# Naninator.net
KiCad netlist of a schematic drawn in EAGLE
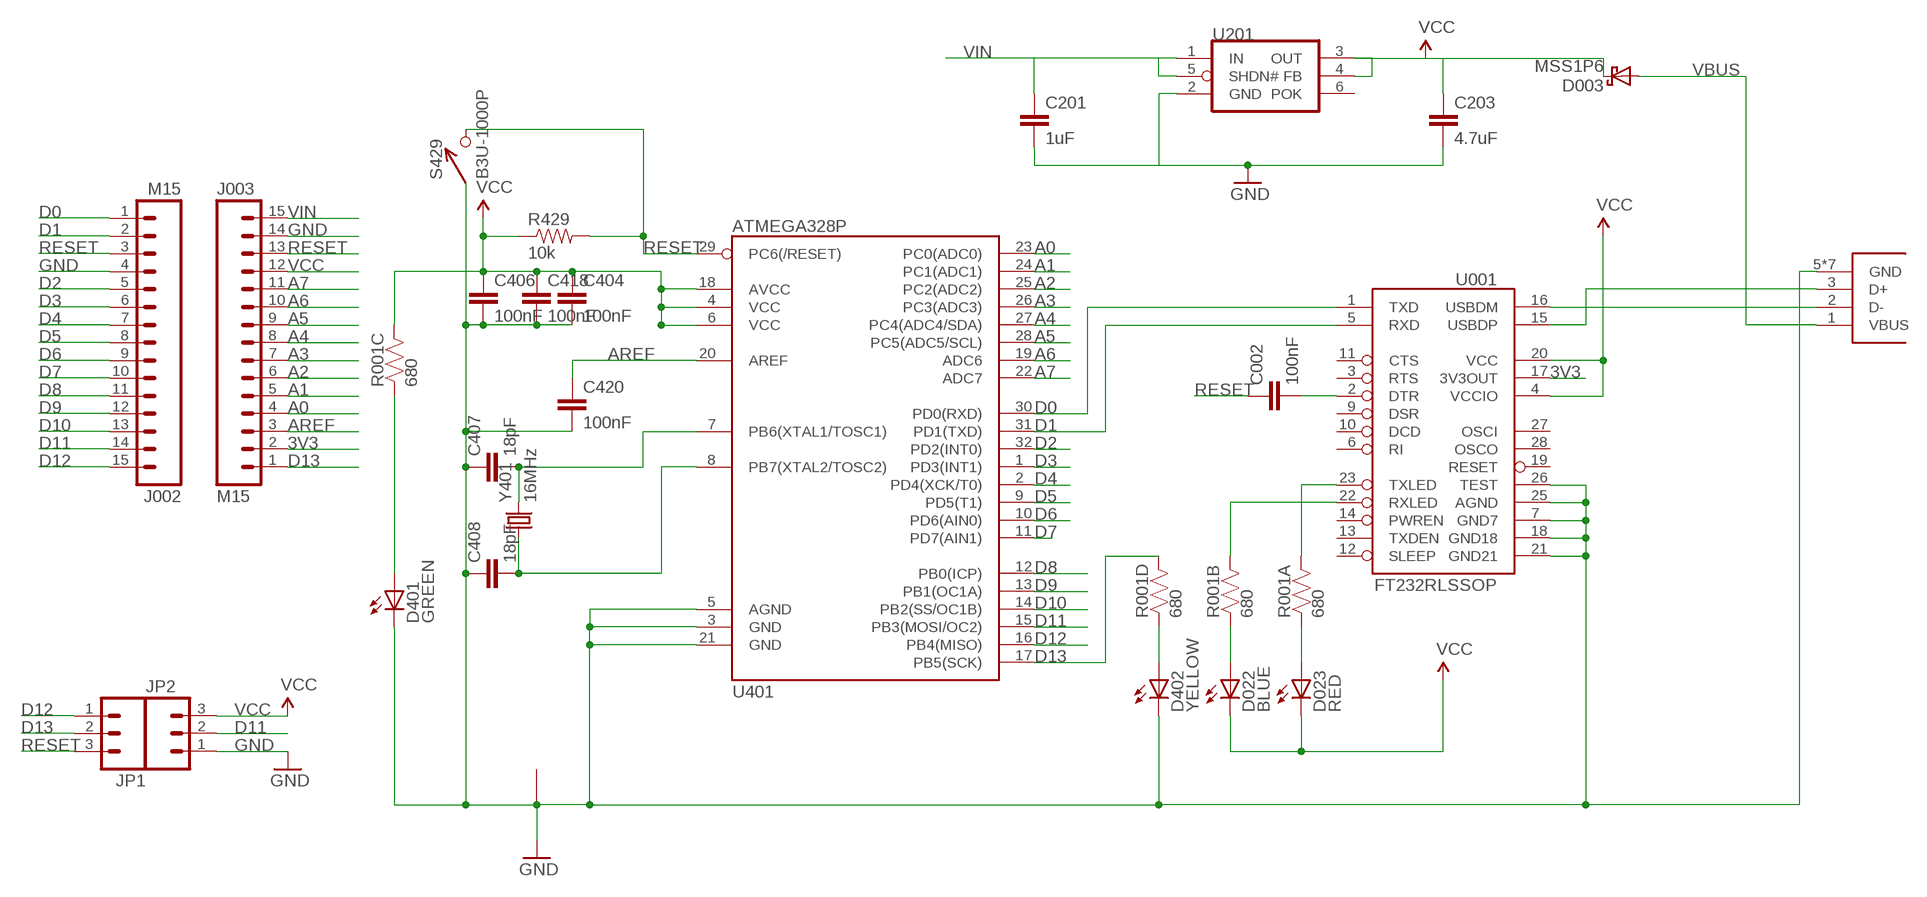
[diagram p0: schematic, sheet 1]

(export (version "E")
  (design (tool "Eeschema 10.0.6"))
  (components
    (comp (ref "C002")
      (value "100nF")
      (footprint "eagle-import:0402-CAP")
      (libsource (lib "eagle-import") (part "CAP0402-CAP"))
    )
    (comp (ref "C201")
      (value "1uF")
      (footprint "eagle-import:0402-CAP")
      (libsource (lib "eagle-import") (part "CAP0402-CAP"))
    )
    (comp (ref "C203")
      (value "4.7uF")
      (footprint "eagle-import:0402-CAP")
      (libsource (lib "eagle-import") (part "CAP0402-CAP"))
    )
    (comp (ref "C404")
      (value "100nF")
      (footprint "eagle-import:0402-CAP")
      (libsource (lib "eagle-import") (part "CAP0402-CAP"))
    )
    (comp (ref "C406")
      (value "100nF")
      (footprint "eagle-import:0402-CAP")
      (libsource (lib "eagle-import") (part "CAP0402-CAP"))
    )
    (comp (ref "C407")
      (value "18pF")
      (footprint "eagle-import:0402-CAP")
      (libsource (lib "eagle-import") (part "CAP0402-CAP"))
    )
    (comp (ref "C408")
      (value "18pF")
      (footprint "eagle-import:0402-CAP")
      (libsource (lib "eagle-import") (part "CAP0402-CAP"))
    )
    (comp (ref "C418")
      (value "100nF")
      (footprint "eagle-import:0402-CAP")
      (libsource (lib "eagle-import") (part "CAP0402-CAP"))
    )
    (comp (ref "C420")
      (value "100nF")
      (footprint "eagle-import:0402-CAP")
      (libsource (lib "eagle-import") (part "CAP0402-CAP"))
    )
    (comp (ref "D003")
      (value "MSS1P6")
      (footprint "eagle-import:MICROSMP")
      (libsource (lib "eagle-import") (part "MSS1P6"))
    )
    (comp (ref "D022")
      (value "BLUE")
      (footprint "eagle-import:LED-0603")
      (libsource (lib "eagle-import") (part "LED0603"))
    )
    (comp (ref "D023")
      (value "RED")
      (footprint "eagle-import:LED-0603")
      (libsource (lib "eagle-import") (part "LED0603"))
    )
    (comp (ref "D401")
      (value "GREEN")
      (footprint "eagle-import:LED-0603")
      (libsource (lib "eagle-import") (part "LED0603"))
    )
    (comp (ref "D402")
      (value "YELLOW")
      (footprint "eagle-import:LED-0603")
      (libsource (lib "eagle-import") (part "LED0603"))
    )
    (comp (ref "J001")
      (value "USB_MICROB_JST")
      (footprint "eagle-import:UB-MC5BR3-SD204-4S")
      (libsource (lib "eagle-import") (part "USB_MICROB_JST"))
    )
    (comp (ref "J002")
      (value "M15")
      (footprint "eagle-import:1X15")
      (libsource (lib "eagle-import") (part "M15"))
    )
    (comp (ref "J003")
      (value "M15")
      (footprint "eagle-import:1X15")
      (libsource (lib "eagle-import") (part "M15"))
    )
    (comp (ref "JP1")
      (value "M03PTH")
      (footprint "eagle-import:1X03")
      (libsource (lib "eagle-import") (part "M03PTH"))
    )
    (comp (ref "JP2")
      (value "M03PTH")
      (footprint "eagle-import:1X03")
      (libsource (lib "eagle-import") (part "M03PTH"))
    )
    (comp (ref "R001")
      (value "680")
      (footprint "eagle-import:CRA04")
      (fields (field (name "DIGIKEY") "CRA4S8680CT-ND"))
      (libsource (lib "eagle-import") (part "RP404"))
    )
    (comp (ref "R429")
      (value "10k")
      (footprint "eagle-import:0402-RES")
      (libsource (lib "eagle-import") (part "RESISTOR0402-RES"))
    )
    (comp (ref "S429")
      (value "B3U-1000P")
      (footprint "eagle-import:B3U-1000P")
      (libsource (lib "eagle-import") (part "B3U-1000P"))
    )
    (comp (ref "U001")
      (value "FT232RLSSOP")
      (footprint "eagle-import:SSOP28DB")
      (libsource (lib "eagle-import") (part "FT232RLSSOP"))
    )
    (comp (ref "U201")
      (value "MAX8881")
      (footprint "eagle-import:SOT-23-6")
      (libsource (lib "eagle-import") (part "MAX8881"))
    )
    (comp (ref "U401")
      (value "ATMEGA328P")
      (footprint "eagle-import:TQFP32-08")
      (libsource (lib "eagle-import") (part "ATMEGA168"))
    )
    (comp (ref "Y401")
      (value "16MHz")
      (footprint "eagle-import:CRYSTAL_SMD_2MM_2_5MM")
      (fields (field (name "DIGIKEY") "478-6955-1-ND"))
      (libsource (lib "eagle-import") (part "CX2520"))
    )
  )
  (nets
    (net (code "1") (name "/3V3") (class "Default")
      (node (ref "J003") (pin "2") (pinfunction "2_2") (pintype "passive"))
      (node (ref "U001") (pin "17") (pinfunction "3V3OUT_17") (pintype "output"))
    )
    (net (code "2") (name "/A0") (class "Default")
      (node (ref "J003") (pin "4") (pinfunction "4_4") (pintype "passive"))
      (node (ref "U401") (pin "23") (pinfunction "PC0(ADC0)_23") (pintype "bidirectional"))
    )
    (net (code "3") (name "/A1") (class "Default")
      (node (ref "J003") (pin "5") (pinfunction "5_5") (pintype "passive"))
      (node (ref "U401") (pin "24") (pinfunction "PC1(ADC1)_24") (pintype "bidirectional"))
    )
    (net (code "4") (name "/A2") (class "Default")
      (node (ref "J003") (pin "6") (pinfunction "6_6") (pintype "passive"))
      (node (ref "U401") (pin "25") (pinfunction "PC2(ADC2)_25") (pintype "bidirectional"))
    )
    (net (code "5") (name "/A3") (class "Default")
      (node (ref "J003") (pin "7") (pinfunction "7_7") (pintype "passive"))
      (node (ref "U401") (pin "26") (pinfunction "PC3(ADC3)_26") (pintype "bidirectional"))
    )
    (net (code "6") (name "/A4") (class "Default")
      (node (ref "J003") (pin "8") (pinfunction "8_8") (pintype "passive"))
      (node (ref "U401") (pin "27") (pinfunction "PC4(ADC4/SDA)_27") (pintype "bidirectional"))
    )
    (net (code "7") (name "/A5") (class "Default")
      (node (ref "J003") (pin "9") (pinfunction "9_9") (pintype "passive"))
      (node (ref "U401") (pin "28") (pinfunction "PC5(ADC5/SCL)_28") (pintype "bidirectional"))
    )
    (net (code "8") (name "/A6") (class "Default")
      (node (ref "J003") (pin "10") (pinfunction "10_10") (pintype "passive"))
      (node (ref "U401") (pin "19") (pinfunction "ADC6_19") (pintype "bidirectional"))
    )
    (net (code "9") (name "/A7") (class "Default")
      (node (ref "J003") (pin "11") (pinfunction "11_11") (pintype "passive"))
      (node (ref "U401") (pin "22") (pinfunction "ADC7_22") (pintype "bidirectional"))
    )
    (net (code "10") (name "/AREF") (class "Default")
      (node (ref "C420") (pin "1") (pinfunction "1_1") (pintype "passive"))
      (node (ref "J003") (pin "3") (pinfunction "3_3") (pintype "passive"))
      (node (ref "U401") (pin "20") (pinfunction "AREF_20") (pintype "bidirectional"))
    )
    (net (code "11") (name "/D0") (class "Default")
      (node (ref "J002") (pin "1") (pinfunction "1_1") (pintype "passive"))
      (node (ref "U001") (pin "1") (pinfunction "TXD_1") (pintype "output"))
      (node (ref "U401") (pin "30") (pinfunction "PD0(RXD)_30") (pintype "bidirectional"))
    )
    (net (code "12") (name "/D1") (class "Default")
      (node (ref "J002") (pin "2") (pinfunction "2_2") (pintype "passive"))
      (node (ref "U001") (pin "5") (pinfunction "RXD_5") (pintype "input"))
      (node (ref "U401") (pin "31") (pinfunction "PD1(TXD)_31") (pintype "bidirectional"))
    )
    (net (code "13") (name "/D2") (class "Default")
      (node (ref "J002") (pin "5") (pinfunction "5_5") (pintype "passive"))
      (node (ref "U401") (pin "32") (pinfunction "PD2(INT0)_32") (pintype "bidirectional"))
    )
    (net (code "14") (name "/D3") (class "Default")
      (node (ref "J002") (pin "6") (pinfunction "6_6") (pintype "passive"))
      (node (ref "U401") (pin "1") (pinfunction "PD3(INT1)_1") (pintype "bidirectional"))
    )
    (net (code "15") (name "/D4") (class "Default")
      (node (ref "J002") (pin "7") (pinfunction "7_7") (pintype "passive"))
      (node (ref "U401") (pin "2") (pinfunction "PD4(XCK/T0)_2") (pintype "bidirectional"))
    )
    (net (code "16") (name "/D5") (class "Default")
      (node (ref "J002") (pin "8") (pinfunction "8_8") (pintype "passive"))
      (node (ref "U401") (pin "9") (pinfunction "PD5(T1)_9") (pintype "bidirectional"))
    )
    (net (code "17") (name "/D6") (class "Default")
      (node (ref "J002") (pin "9") (pinfunction "9_9") (pintype "passive"))
      (node (ref "U401") (pin "10") (pinfunction "PD6(AIN0)_10") (pintype "bidirectional"))
    )
    (net (code "18") (name "/D7") (class "Default")
      (node (ref "J002") (pin "10") (pinfunction "10_10") (pintype "passive"))
      (node (ref "U401") (pin "11") (pinfunction "PD7(AIN1)_11") (pintype "bidirectional"))
    )
    (net (code "19") (name "/D8") (class "Default")
      (node (ref "J002") (pin "11") (pinfunction "11_11") (pintype "passive"))
      (node (ref "U401") (pin "12") (pinfunction "PB0(ICP)_12") (pintype "bidirectional"))
    )
    (net (code "20") (name "/D9") (class "Default")
      (node (ref "J002") (pin "12") (pinfunction "12_12") (pintype "passive"))
      (node (ref "U401") (pin "13") (pinfunction "PB1(OC1A)_13") (pintype "bidirectional"))
    )
    (net (code "21") (name "/D10") (class "Default")
      (node (ref "J002") (pin "13") (pinfunction "13_13") (pintype "passive"))
      (node (ref "U401") (pin "14") (pinfunction "PB2(SS/OC1B)_14") (pintype "bidirectional"))
    )
    (net (code "22") (name "/D11") (class "Default")
      (node (ref "J002") (pin "14") (pinfunction "14_14") (pintype "passive"))
      (node (ref "JP2") (pin "2") (pinfunction "2_2") (pintype "passive"))
      (node (ref "U401") (pin "15") (pinfunction "PB3(MOSI/OC2)_15") (pintype "bidirectional"))
    )
    (net (code "23") (name "/D12") (class "Default")
      (node (ref "J002") (pin "15") (pinfunction "15_15") (pintype "passive"))
      (node (ref "JP1") (pin "1") (pinfunction "1_1") (pintype "passive"))
      (node (ref "U401") (pin "16") (pinfunction "PB4(MISO)_16") (pintype "bidirectional"))
    )
    (net (code "24") (name "/D13") (class "Default")
      (node (ref "J003") (pin "1") (pinfunction "1_1") (pintype "passive"))
      (node (ref "JP1") (pin "2") (pinfunction "2_2") (pintype "passive"))
      (node (ref "R001") (pin "5") (pinfunction "2_5") (pintype "passive"))
      (node (ref "U401") (pin "17") (pinfunction "PB5(SCK)_17") (pintype "bidirectional"))
    )
    (net (code "25") (name "/RESET") (class "Default")
      (node (ref "C002") (pin "1") (pinfunction "1_1") (pintype "passive"))
      (node (ref "J002") (pin "3") (pinfunction "3_3") (pintype "passive"))
      (node (ref "J003") (pin "13") (pinfunction "13_13") (pintype "passive"))
      (node (ref "JP1") (pin "3") (pinfunction "3_3") (pintype "passive"))
      (node (ref "R429") (pin "2") (pinfunction "2_2") (pintype "passive"))
      (node (ref "S429") (pin "P$2") (pinfunction "2_P$2") (pintype "bidirectional"))
      (node (ref "U401") (pin "29") (pinfunction "PC6(/RESET)_29") (pintype "bidirectional"))
    )
    (net (code "26") (name "/VBUS") (class "Default")
      (node (ref "D003") (pin "A") (pinfunction "A_A") (pintype "passive"))
      (node (ref "J001") (pin "1") (pinfunction "VBUS_1") (pintype "bidirectional"))
    )
    (net (code "27") (name "/VIN") (class "Default")
      (node (ref "C201") (pin "1") (pinfunction "1_1") (pintype "passive"))
      (node (ref "J003") (pin "15") (pinfunction "15_15") (pintype "passive"))
      (node (ref "U201") (pin "1") (pinfunction "IN_1") (pintype "bidirectional"))
      (node (ref "U201") (pin "5") (pinfunction "SHDN#_5") (pintype "bidirectional"))
    )
    (net (code "28") (name "GND") (class "Default")
      (node (ref "C201") (pin "2") (pinfunction "2_2") (pintype "passive"))
      (node (ref "C203") (pin "2") (pinfunction "2_2") (pintype "passive"))
      (node (ref "C404") (pin "2") (pinfunction "2_2") (pintype "passive"))
      (node (ref "C406") (pin "2") (pinfunction "2_2") (pintype "passive"))
      (node (ref "C407") (pin "1") (pinfunction "1_1") (pintype "passive"))
      (node (ref "C408") (pin "1") (pinfunction "1_1") (pintype "passive"))
      (node (ref "C418") (pin "2") (pinfunction "2_2") (pintype "passive"))
      (node (ref "C420") (pin "2") (pinfunction "2_2") (pintype "passive"))
      (node (ref "D401") (pin "C") (pinfunction "C_C") (pintype "passive"))
      (node (ref "D402") (pin "C") (pinfunction "C_C") (pintype "passive"))
      (node (ref "J001") (pin "5") (pinfunction "GND_5") (pintype "bidirectional"))
      (node (ref "J001") (pin "P$10") (pinfunction "GND_P$10") (pintype "bidirectional"))
      (node (ref "J001") (pin "P$11") (pinfunction "GND_P$11") (pintype "bidirectional"))
      (node (ref "J001") (pin "P$6") (pinfunction "GND_P$6") (pintype "bidirectional"))
      (node (ref "J001") (pin "P$7") (pinfunction "GND_P$7") (pintype "bidirectional"))
      (node (ref "J001") (pin "P$8") (pinfunction "GND_P$8") (pintype "bidirectional"))
      (node (ref "J001") (pin "P$9") (pinfunction "GND_P$9") (pintype "bidirectional"))
      (node (ref "J002") (pin "4") (pinfunction "4_4") (pintype "passive"))
      (node (ref "J003") (pin "14") (pinfunction "14_14") (pintype "passive"))
      (node (ref "JP2") (pin "1") (pinfunction "1_1") (pintype "passive"))
      (node (ref "S429") (pin "P$1") (pinfunction "1_P$1") (pintype "bidirectional"))
      (node (ref "U001") (pin "18") (pinfunction "GND18_18") (pintype "power_in"))
      (node (ref "U001") (pin "21") (pinfunction "GND21_21") (pintype "power_in"))
      (node (ref "U001") (pin "25") (pinfunction "AGND_25") (pintype "power_in"))
      (node (ref "U001") (pin "26") (pinfunction "TEST_26") (pintype "input"))
      (node (ref "U001") (pin "7") (pinfunction "GND7_7") (pintype "power_in"))
      (node (ref "U201") (pin "2") (pinfunction "GND_2") (pintype "bidirectional"))
      (node (ref "U401") (pin "21") (pinfunction "GND_21") (pintype "bidirectional"))
      (node (ref "U401") (pin "3") (pinfunction "GND_3") (pintype "bidirectional"))
      (node (ref "U401") (pin "5") (pinfunction "AGND_5") (pintype "bidirectional"))
      (node (ref "Y401") (pin "2") (pinfunction "1_2") (pintype "bidirectional"))
      (node (ref "Y401") (pin "4") (pinfunction "1_4") (pintype "bidirectional"))
    )
    (net (code "29") (name "Net-(D023-PadA)") (class "Default")
      (node (ref "D023") (pin "A") (pinfunction "A_A") (pintype "passive"))
      (node (ref "R001") (pin "1") (pinfunction "1_1") (pintype "passive"))
    )
    (net (code "30") (name "Net-(J001-D+)") (class "Default")
      (node (ref "J001") (pin "3") (pinfunction "D+_3") (pintype "bidirectional"))
      (node (ref "U001") (pin "15") (pinfunction "USBDP_15") (pintype "bidirectional"))
    )
    (net (code "31") (name "Net-(J001-D-)") (class "Default")
      (node (ref "J001") (pin "2") (pinfunction "D-_2") (pintype "bidirectional"))
      (node (ref "U001") (pin "16") (pinfunction "USBDM_16") (pintype "bidirectional"))
    )
    (net (code "32") (name "Net-(R001A-2)") (class "Default")
      (node (ref "R001") (pin "8") (pinfunction "2_8") (pintype "passive"))
      (node (ref "U001") (pin "23") (pinfunction "TXLED_23") (pintype "input"))
    )
    (net (code "33") (name "Net-(R001B-1)") (class "Default")
      (node (ref "D022") (pin "A") (pinfunction "A_A") (pintype "passive"))
      (node (ref "R001") (pin "2") (pinfunction "1_2") (pintype "passive"))
    )
    (net (code "34") (name "Net-(R001B-2)") (class "Default")
      (node (ref "R001") (pin "7") (pinfunction "2_7") (pintype "passive"))
      (node (ref "U001") (pin "22") (pinfunction "RXLED_22") (pintype "input"))
    )
    (net (code "35") (name "Net-(R001C-1)") (class "Default")
      (node (ref "D401") (pin "A") (pinfunction "A_A") (pintype "passive"))
      (node (ref "R001") (pin "3") (pinfunction "1_3") (pintype "passive"))
    )
    (net (code "36") (name "Net-(R001D-1)") (class "Default")
      (node (ref "D402") (pin "A") (pinfunction "A_A") (pintype "passive"))
      (node (ref "R001") (pin "4") (pinfunction "1_4") (pintype "passive"))
    )
    (net (code "37") (name "Net-(U001-DTR)") (class "Default")
      (node (ref "C002") (pin "2") (pinfunction "2_2") (pintype "passive"))
      (node (ref "U001") (pin "2") (pinfunction "DTR_2") (pintype "output"))
    )
    (net (code "38") (name "Net-(U401-PB6(XTAL1{slash}TOSC1))") (class "Default")
      (node (ref "C407") (pin "2") (pinfunction "2_2") (pintype "passive"))
      (node (ref "U401") (pin "7") (pinfunction "PB6(XTAL1/TOSC1)_7") (pintype "bidirectional"))
      (node (ref "Y401") (pin "3") (pinfunction "2_3") (pintype "passive"))
    )
    (net (code "39") (name "Net-(U401-PB7(XTAL2{slash}TOSC2))") (class "Default")
      (node (ref "C408") (pin "2") (pinfunction "2_2") (pintype "passive"))
      (node (ref "U401") (pin "8") (pinfunction "PB7(XTAL2/TOSC2)_8") (pintype "bidirectional"))
      (node (ref "Y401") (pin "1") (pinfunction "1_1") (pintype "passive"))
    )
    (net (code "40") (name "VCC") (class "Default")
      (node (ref "C203") (pin "1") (pinfunction "1_1") (pintype "passive"))
      (node (ref "C404") (pin "1") (pinfunction "1_1") (pintype "passive"))
      (node (ref "C406") (pin "1") (pinfunction "1_1") (pintype "passive"))
      (node (ref "C418") (pin "1") (pinfunction "1_1") (pintype "passive"))
      (node (ref "D003") (pin "K") (pinfunction "K_K") (pintype "passive"))
      (node (ref "D022") (pin "C") (pinfunction "C_C") (pintype "passive"))
      (node (ref "D023") (pin "C") (pinfunction "C_C") (pintype "passive"))
      (node (ref "J003") (pin "12") (pinfunction "12_12") (pintype "passive"))
      (node (ref "JP2") (pin "3") (pinfunction "3_3") (pintype "passive"))
      (node (ref "R001") (pin "6") (pinfunction "2_6") (pintype "passive"))
      (node (ref "R429") (pin "1") (pinfunction "1_1") (pintype "passive"))
      (node (ref "U001") (pin "20") (pinfunction "VCC_20") (pintype "power_in"))
      (node (ref "U001") (pin "4") (pinfunction "VCCIO_4") (pintype "power_in"))
      (node (ref "U201") (pin "3") (pinfunction "OUT_3") (pintype "bidirectional"))
      (node (ref "U201") (pin "4") (pinfunction "FB_4") (pintype "bidirectional"))
      (node (ref "U401") (pin "18") (pinfunction "AVCC_18") (pintype "bidirectional"))
      (node (ref "U401") (pin "4") (pinfunction "VCC_4") (pintype "bidirectional"))
      (node (ref "U401") (pin "6") (pinfunction "VCC_6") (pintype "bidirectional"))
    )
    (net (code "41") (name "unconnected-(U001-CTS-Pad11)") (class "Default")
      (node (ref "U001") (pin "11") (pinfunction "CTS_11") (pintype "input"))
    )
    (net (code "42") (name "unconnected-(U001-DCD-Pad10)") (class "Default")
      (node (ref "U001") (pin "10") (pinfunction "DCD_10") (pintype "input"))
    )
    (net (code "43") (name "unconnected-(U001-DSR-Pad9)") (class "Default")
      (node (ref "U001") (pin "9") (pinfunction "DSR_9") (pintype "input"))
    )
    (net (code "44") (name "unconnected-(U001-OSCI-Pad27)") (class "Default")
      (node (ref "U001") (pin "27") (pinfunction "OSCI_27") (pintype "input"))
    )
    (net (code "45") (name "unconnected-(U001-OSCO-Pad28)") (class "Default")
      (node (ref "U001") (pin "28") (pinfunction "OSCO_28") (pintype "output"))
    )
    (net (code "46") (name "unconnected-(U001-PWREN-Pad14)") (class "Default")
      (node (ref "U001") (pin "14") (pinfunction "PWREN_14") (pintype "input"))
    )
    (net (code "47") (name "unconnected-(U001-RESET-Pad19)") (class "Default")
      (node (ref "U001") (pin "19") (pinfunction "RESET_19") (pintype "input"))
    )
    (net (code "48") (name "unconnected-(U001-RI-Pad6)") (class "Default")
      (node (ref "U001") (pin "6") (pinfunction "RI_6") (pintype "input"))
    )
    (net (code "49") (name "unconnected-(U001-RTS-Pad3)") (class "Default")
      (node (ref "U001") (pin "3") (pinfunction "RTS_3") (pintype "output"))
    )
    (net (code "50") (name "unconnected-(U001-SLEEP-Pad12)") (class "Default")
      (node (ref "U001") (pin "12") (pinfunction "SLEEP_12") (pintype "input"))
    )
    (net (code "51") (name "unconnected-(U001-TXDEN-Pad13)") (class "Default")
      (node (ref "U001") (pin "13") (pinfunction "TXDEN_13") (pintype "input"))
    )
    (net (code "52") (name "unconnected-(U201-POK-Pad6)") (class "Default")
      (node (ref "U201") (pin "6") (pinfunction "POK_6") (pintype "bidirectional"))
    )
  )
)
